# Motorcontroller_V0_6.net
KiCad netlist of a schematic drawn in EAGLE
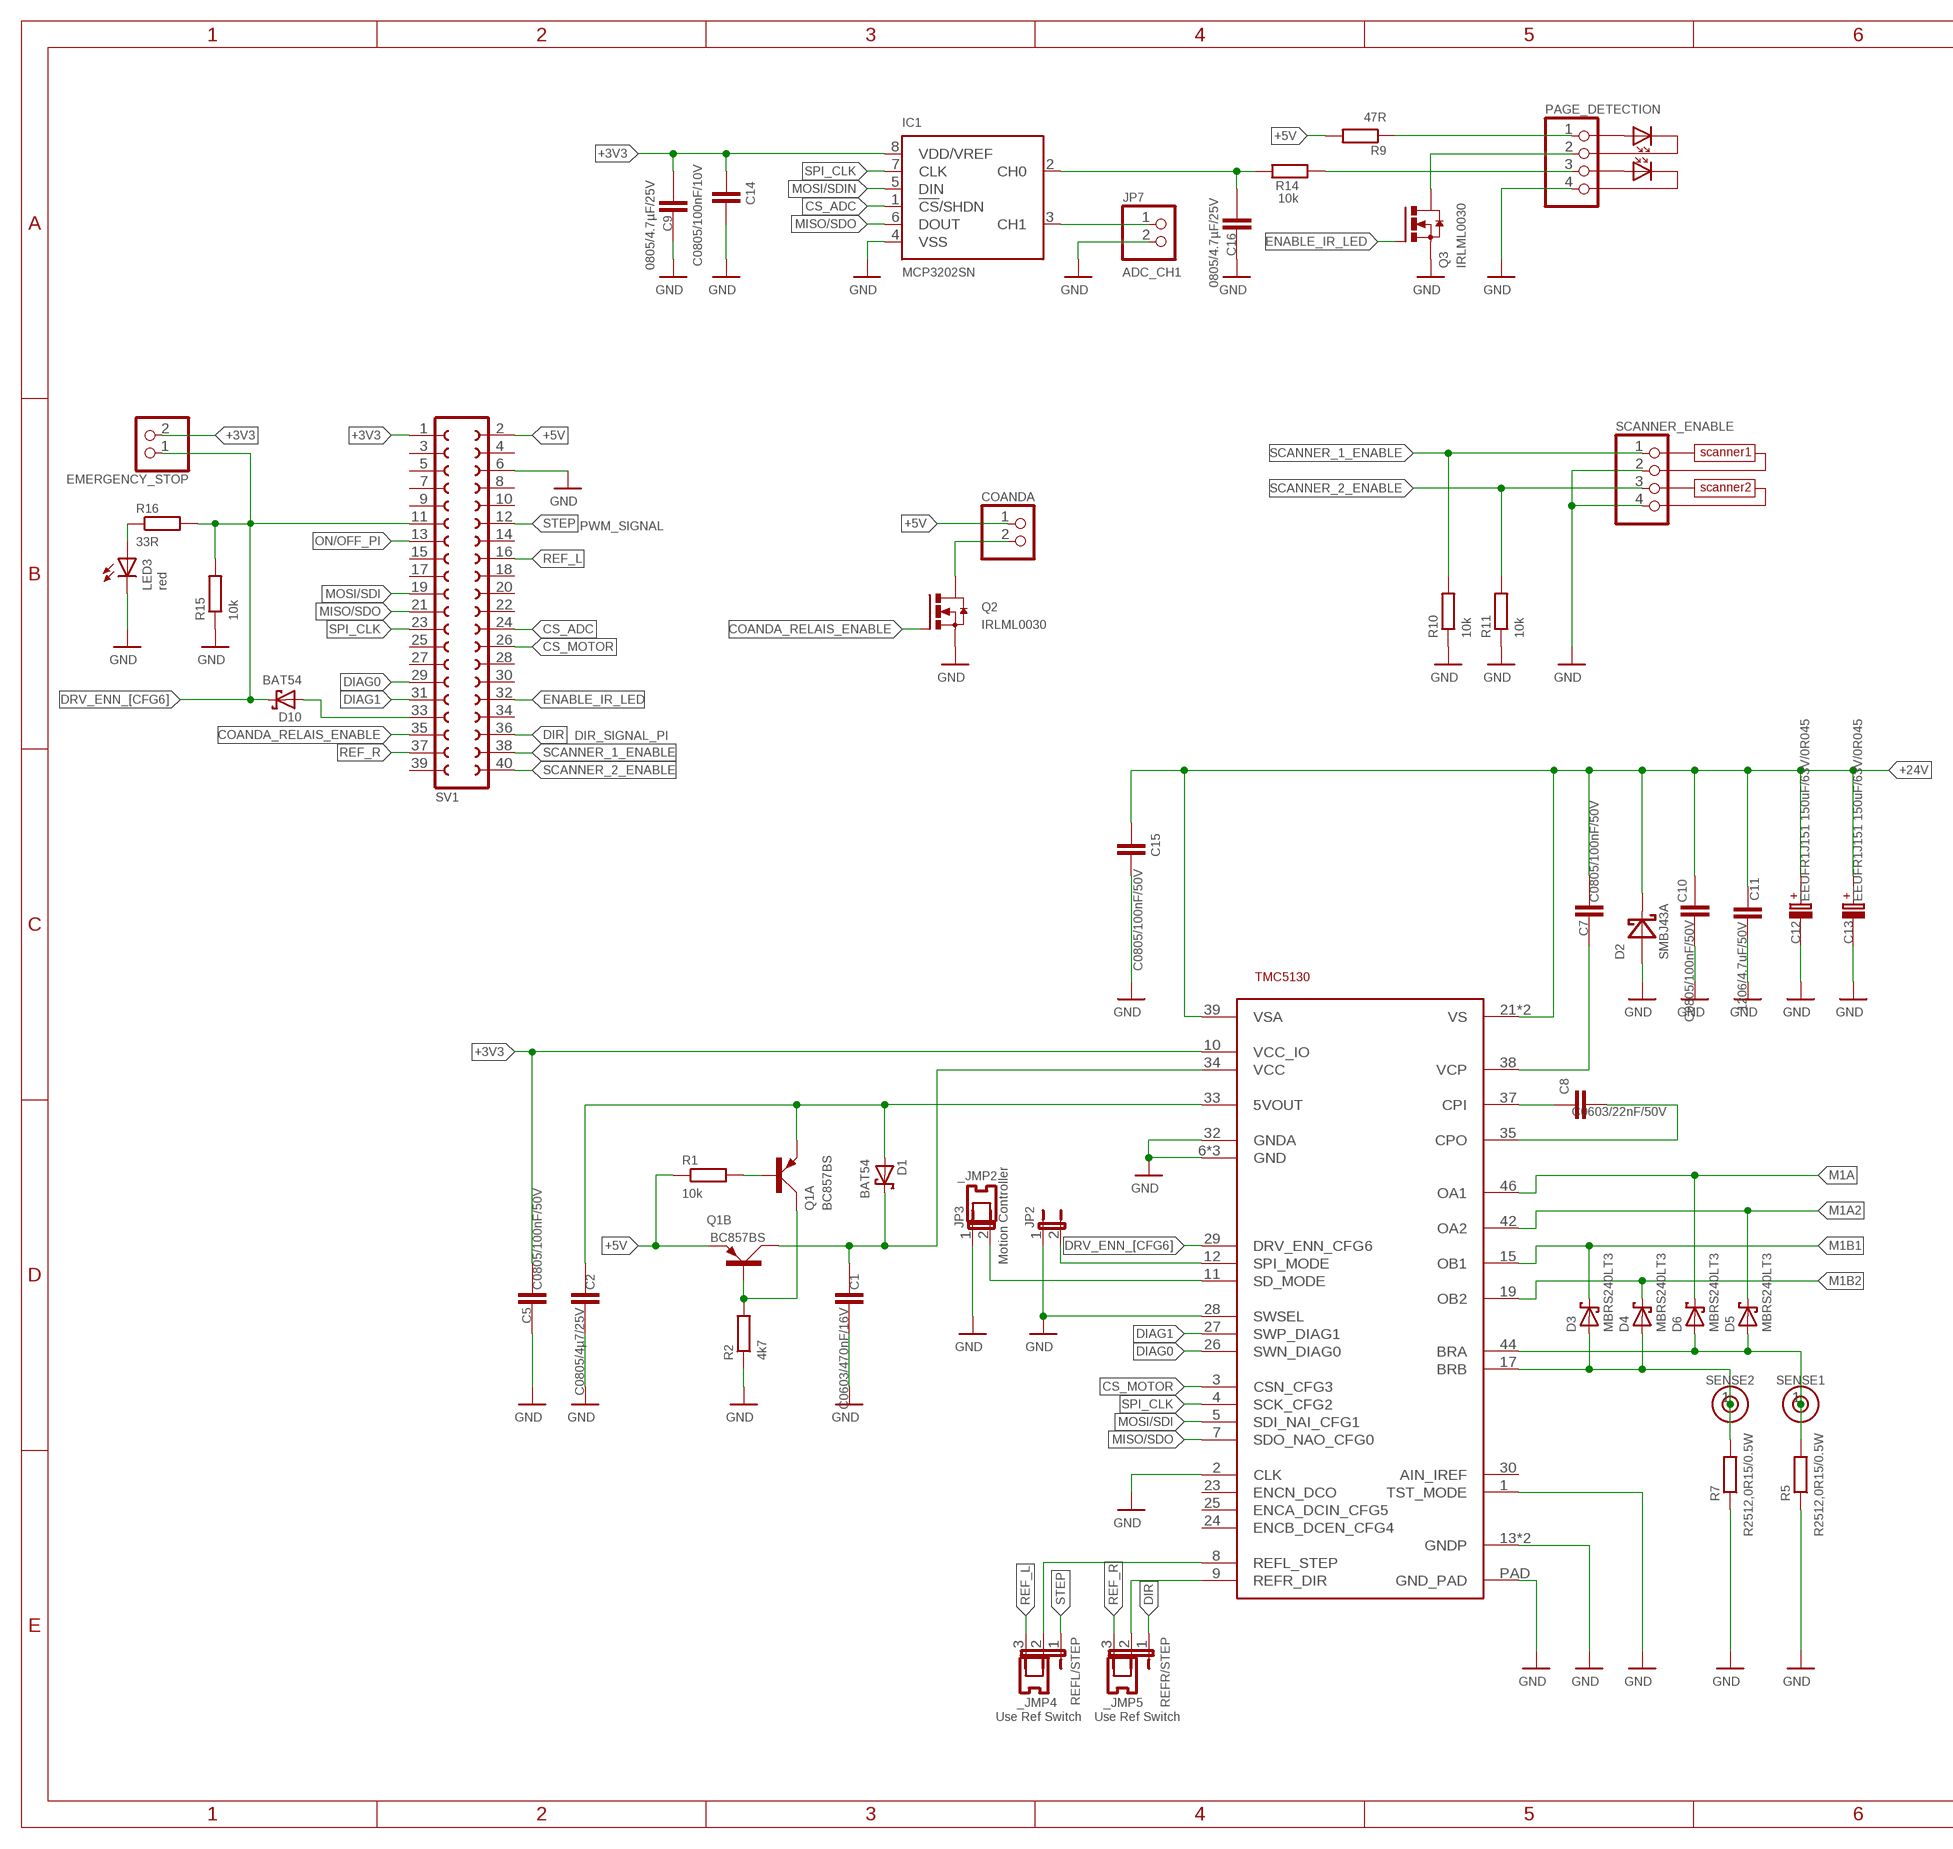
[diagram p0: schematic, sheet 1, part 1 of 2]
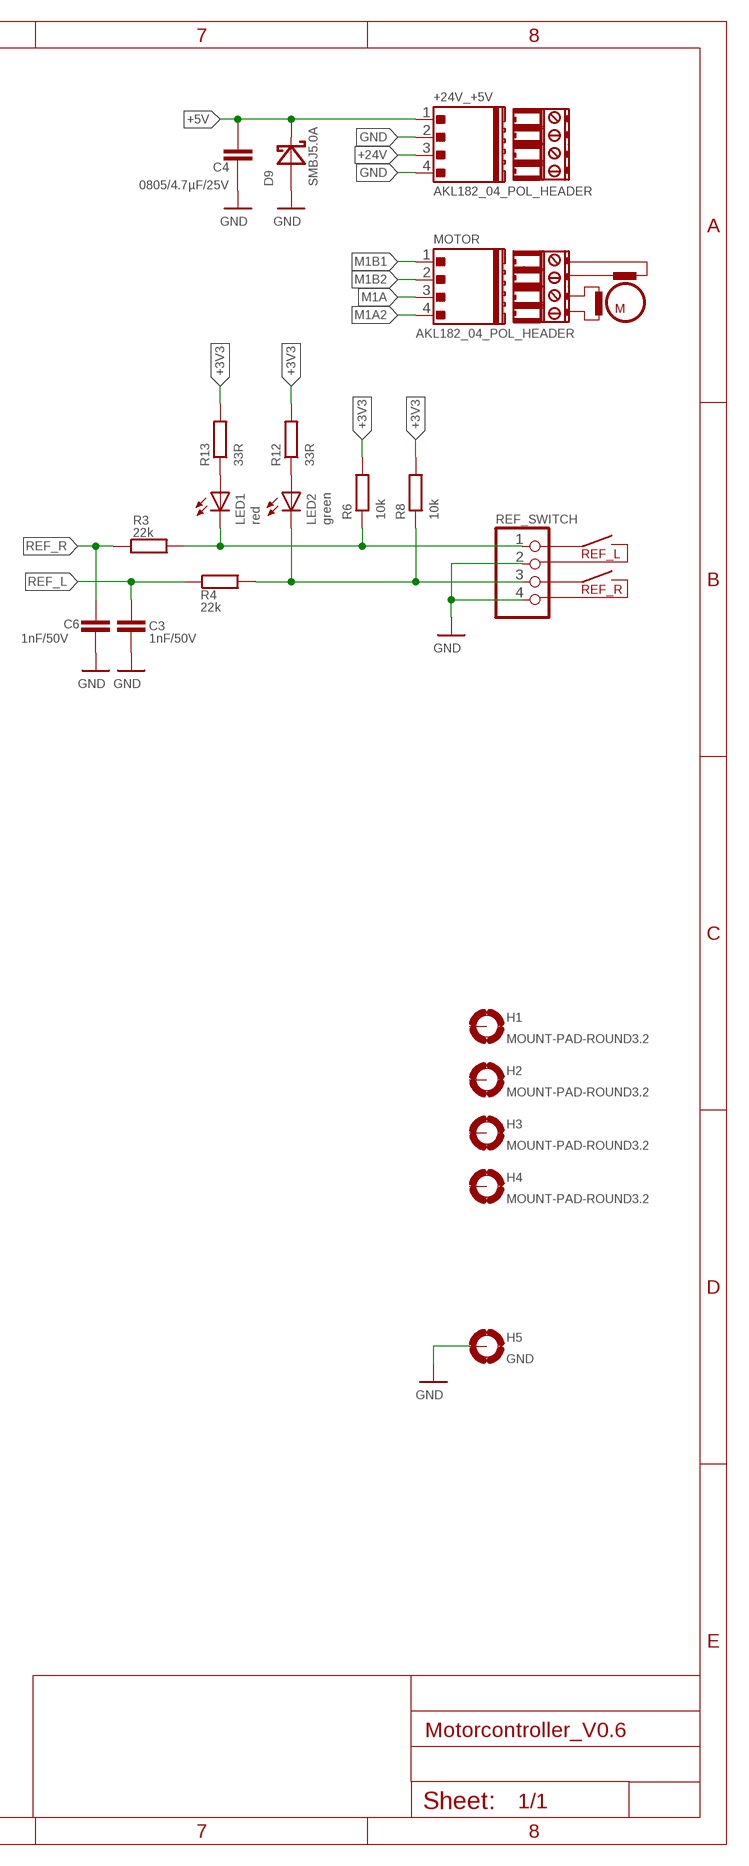
[diagram p1: schematic, sheet 1, part 2 of 2]

(export (version "E")
  (design (tool "Eeschema 10.0.6"))
  (components
    (comp (ref "+24V_+5V")
      (value "AKL182_04_POL_HEADER")
      (footprint "eagle-import:AKL169_04_POL")
      (fields (field (name "1_PARTNUMBER") "31182104") (field (name "2_PARTNUMBER") "AKL 182-04"))
      (libsource (lib "eagle-import") (part "AKL182_04_POL_HEADER"))
    )
    (comp (ref "C1")
      (value "C0603/470nF/16V")
      (footprint "eagle-import:0603")
      (libsource (lib "eagle-import") (part "C/0603"))
    )
    (comp (ref "C2")
      (value "C0805/4µ7/25V")
      (footprint "eagle-import:0805")
      (libsource (lib "eagle-import") (part "C/0805"))
    )
    (comp (ref "C3")
      (value "1nF/50V")
      (footprint "eagle-import:C0603K")
      (libsource (lib "eagle-import") (part "C-EUC0603K"))
    )
    (comp (ref "C4")
      (value "0805/4.7µF/25V")
      (footprint "eagle-import:RCL_0805")
      (libsource (lib "eagle-import") (part "RCL_C/0805"))
    )
    (comp (ref "C5")
      (value "C0805/100nF/50V")
      (footprint "eagle-import:0805")
      (libsource (lib "eagle-import") (part "C/0805"))
    )
    (comp (ref "C6")
      (value "1nF/50V")
      (footprint "eagle-import:C0603K")
      (libsource (lib "eagle-import") (part "C-EUC0603K"))
    )
    (comp (ref "C7")
      (value "C0805/100nF/50V")
      (footprint "eagle-import:0805")
      (libsource (lib "eagle-import") (part "C/0805"))
    )
    (comp (ref "C8")
      (value "C0603/22nF/50V")
      (footprint "eagle-import:C0603")
      (libsource (lib "eagle-import") (part "C-EUC0603"))
    )
    (comp (ref "C9")
      (value "0805/4.7µF/25V")
      (footprint "eagle-import:RCL_0805")
      (libsource (lib "eagle-import") (part "RCL_C/0805"))
    )
    (comp (ref "C10")
      (value "C0805/100nF/50V")
      (footprint "eagle-import:0805")
      (libsource (lib "eagle-import") (part "C/0805"))
    )
    (comp (ref "C11")
      (value "1206/4.7uF/50V")
      (footprint "eagle-import:C1206")
      (libsource (lib "eagle-import") (part "C-EUC1206"))
    )
    (comp (ref "C12")
      (value "EEUFR1J151 150uF/63V/0R045")
      (footprint "eagle-import:C_POL_RAD_THT_5X10X12.5")
      (libsource (lib "eagle-import") (part "C_POL"))
    )
    (comp (ref "C13")
      (value "EEUFR1J151 150uF/63V/0R045")
      (footprint "eagle-import:C_POL_RAD_THT_5X10X12.5")
      (libsource (lib "eagle-import") (part "C_POL"))
    )
    (comp (ref "C14")
      (value "C0805/100nF/10V")
      (footprint "eagle-import:C0805")
      (libsource (lib "eagle-import") (part "C-EUC0805"))
    )
    (comp (ref "C15")
      (value "C0805/100nF/50V")
      (footprint "eagle-import:C0805")
      (libsource (lib "eagle-import") (part "C-EUC0805"))
    )
    (comp (ref "C16")
      (value "0805/4.7µF/25V")
      (footprint "eagle-import:RCL_0805")
      (libsource (lib "eagle-import") (part "RCL_C/0805"))
    )
    (comp (ref "COANDA")
      (value "PINHD-1X2")
      (footprint "eagle-import:1X02")
      (libsource (lib "eagle-import") (part "PINHD-1X2"))
    )
    (comp (ref "D1")
      (value "BAT54")
      (footprint "eagle-import:SOT23")
      (libsource (lib "eagle-import") (part "BAT54"))
    )
    (comp (ref "D2")
      (value "SMBJ43A")
      (footprint "eagle-import:SMB")
      (libsource (lib "eagle-import") (part "SMBJ"))
    )
    (comp (ref "D3")
      (value "MBRS240LT3")
      (footprint "eagle-import:SMB")
      (libsource (lib "eagle-import") (part "MBRS130LT3"))
    )
    (comp (ref "D4")
      (value "MBRS240LT3")
      (footprint "eagle-import:SMB")
      (libsource (lib "eagle-import") (part "MBRS130LT3"))
    )
    (comp (ref "D5")
      (value "MBRS240LT3")
      (footprint "eagle-import:SMB")
      (libsource (lib "eagle-import") (part "MBRS130LT3"))
    )
    (comp (ref "D6")
      (value "MBRS240LT3")
      (footprint "eagle-import:SMB")
      (libsource (lib "eagle-import") (part "MBRS130LT3"))
    )
    (comp (ref "D9")
      (value "SMBJ5.0A")
      (footprint "eagle-import:SMB")
      (libsource (lib "eagle-import") (part "SMBJ"))
    )
    (comp (ref "D10")
      (value "BAT54")
      (footprint "eagle-import:SOT23")
      (libsource (lib "eagle-import") (part "BAT54"))
    )
    (comp (ref "EMERGENCY_STOP")
      (value "PINHD-1X2")
      (footprint "eagle-import:1X02")
      (libsource (lib "eagle-import") (part "PINHD-1X2"))
    )
    (comp (ref "H1")
      (value "MOUNT-PAD-ROUND3.2")
      (footprint "eagle-import:3,2-PAD")
      (libsource (lib "eagle-import") (part "MOUNT-PAD-ROUND3.2"))
    )
    (comp (ref "H2")
      (value "MOUNT-PAD-ROUND3.2")
      (footprint "eagle-import:3,2-PAD")
      (libsource (lib "eagle-import") (part "MOUNT-PAD-ROUND3.2"))
    )
    (comp (ref "H3")
      (value "MOUNT-PAD-ROUND3.2")
      (footprint "eagle-import:3,2-PAD")
      (libsource (lib "eagle-import") (part "MOUNT-PAD-ROUND3.2"))
    )
    (comp (ref "H4")
      (value "MOUNT-PAD-ROUND3.2")
      (footprint "eagle-import:3,2-PAD")
      (libsource (lib "eagle-import") (part "MOUNT-PAD-ROUND3.2"))
    )
    (comp (ref "H5")
      (value "GND")
      (footprint "eagle-import:3,2-PAD")
      (libsource (lib "eagle-import") (part "MOUNT-PAD-ROUND3.2"))
    )
    (comp (ref "IC1")
      (value "MCP3202SN")
      (footprint "eagle-import:SO-08")
      (fields (field (name "MF") "MICROCHIP") (field (name "MPN") "MCP3202-CI/SN"))
      (libsource (lib "eagle-import") (part "MCP3202SN"))
    )
    (comp (ref "JP2")
      (value "JP1E")
      (footprint "eagle-import:JP1")
      (libsource (lib "eagle-import") (part "JP1E"))
    )
    (comp (ref "JP3")
      (value "JP1E")
      (footprint "eagle-import:JP1")
      (libsource (lib "eagle-import") (part "JP1E"))
    )
    (comp (ref "JP7")
      (value "ADC_CH1")
      (footprint "eagle-import:1X02")
      (libsource (lib "eagle-import") (part "PINHD-1X2"))
    )
    (comp (ref "LED1")
      (value "red")
      (footprint "eagle-import:CHIP-LED0805")
      (libsource (lib "eagle-import") (part "LEDCHIP-LED0805"))
    )
    (comp (ref "LED2")
      (value "green")
      (footprint "eagle-import:CHIP-LED0805")
      (libsource (lib "eagle-import") (part "LEDCHIP-LED0805"))
    )
    (comp (ref "LED3")
      (value "red")
      (footprint "eagle-import:CHIP-LED0805")
      (libsource (lib "eagle-import") (part "LEDCHIP-LED0805"))
    )
    (comp (ref "MOTOR")
      (value "AKL182_04_POL_HEADER")
      (footprint "eagle-import:AKL169_04_POL")
      (fields (field (name "1_PARTNUMBER") "31182104") (field (name "2_PARTNUMBER") "AKL 182-04"))
      (libsource (lib "eagle-import") (part "AKL182_04_POL_HEADER"))
    )
    (comp (ref "PAGE_DETECTION")
      (value "PINHD-1X4")
      (footprint "eagle-import:1X04")
      (libsource (lib "eagle-import") (part "PINHD-1X4"))
    )
    (comp (ref "Q1")
      (value "BC857BS")
      (footprint "eagle-import:SOT363_PHILIPS")
      (libsource (lib "eagle-import") (part "BC857BS"))
    )
    (comp (ref "Q2")
      (value "IRLML0030")
      (footprint "eagle-import:SOT-23")
      (libsource (lib "eagle-import") (part "IRLML0030"))
    )
    (comp (ref "Q3")
      (value "IRLML0030")
      (footprint "eagle-import:SOT-23")
      (libsource (lib "eagle-import") (part "IRLML0030"))
    )
    (comp (ref "R1")
      (value "10k")
      (footprint "eagle-import:M0805")
      (libsource (lib "eagle-import") (part "R-EU_M0805"))
    )
    (comp (ref "R2")
      (value "4k7")
      (footprint "eagle-import:M0805")
      (libsource (lib "eagle-import") (part "R-EU_M0805"))
    )
    (comp (ref "R3")
      (value "22k")
      (footprint "eagle-import:R0603")
      (libsource (lib "eagle-import") (part "R-EU_R0603"))
    )
    (comp (ref "R4")
      (value "22k")
      (footprint "eagle-import:R0603")
      (libsource (lib "eagle-import") (part "R-EU_R0603"))
    )
    (comp (ref "R5")
      (value "R2512,0R15/0.5W")
      (footprint "eagle-import:R2512")
      (libsource (lib "eagle-import") (part "R-EU_R2512"))
    )
    (comp (ref "R6")
      (value "10k")
      (footprint "eagle-import:M0805")
      (libsource (lib "eagle-import") (part "R-EU_M0805"))
    )
    (comp (ref "R7")
      (value "R2512,0R15/0.5W")
      (footprint "eagle-import:R2512")
      (libsource (lib "eagle-import") (part "R-EU_R2512"))
    )
    (comp (ref "R8")
      (value "10k")
      (footprint "eagle-import:M0805")
      (libsource (lib "eagle-import") (part "R-EU_M0805"))
    )
    (comp (ref "R9")
      (value "47R")
      (footprint "eagle-import:M1206")
      (libsource (lib "eagle-import") (part "R-EU_M1206"))
    )
    (comp (ref "R10")
      (value "10k")
      (footprint "eagle-import:M0805")
      (libsource (lib "eagle-import") (part "R-EU_M0805"))
    )
    (comp (ref "R11")
      (value "10k")
      (footprint "eagle-import:M0805")
      (libsource (lib "eagle-import") (part "R-EU_M0805"))
    )
    (comp (ref "R12")
      (value "33R")
      (footprint "eagle-import:M0805")
      (libsource (lib "eagle-import") (part "R-EU_M0805"))
    )
    (comp (ref "R13")
      (value "33R")
      (footprint "eagle-import:M0805")
      (libsource (lib "eagle-import") (part "R-EU_M0805"))
    )
    (comp (ref "R14")
      (value "10k")
      (footprint "eagle-import:M0805")
      (libsource (lib "eagle-import") (part "R-EU_M0805"))
    )
    (comp (ref "R15")
      (value "10k")
      (footprint "eagle-import:M0805")
      (libsource (lib "eagle-import") (part "R-EU_M0805"))
    )
    (comp (ref "R16")
      (value "33R")
      (footprint "eagle-import:M0805")
      (libsource (lib "eagle-import") (part "R-EU_M0805"))
    )
    (comp (ref "REFL/STEP")
      (value "JP2E")
      (footprint "eagle-import:JP2")
      (libsource (lib "eagle-import") (part "JP2E"))
    )
    (comp (ref "REFR/STEP")
      (value "JP2E")
      (footprint "eagle-import:JP2")
      (libsource (lib "eagle-import") (part "JP2E"))
    )
    (comp (ref "REF_SWITCH")
      (value "PINHD-1X4")
      (footprint "eagle-import:1X04")
      (libsource (lib "eagle-import") (part "PINHD-1X4"))
    )
    (comp (ref "SCANNER_ENABLE")
      (value "PINHD-1X4")
      (footprint "eagle-import:1X04")
      (libsource (lib "eagle-import") (part "PINHD-1X4"))
    )
    (comp (ref "SENSE1")
      (value "1PIN_1ROW")
      (footprint "eagle-import:1PIN_1ROW_THT")
      (libsource (lib "eagle-import") (part "1PIN_1ROW"))
    )
    (comp (ref "SENSE2")
      (value "1PIN_1ROW")
      (footprint "eagle-import:1PIN_1ROW_THT")
      (libsource (lib "eagle-import") (part "1PIN_1ROW"))
    )
    (comp (ref "SV1")
      (value "FE20-2")
      (footprint "eagle-import:FE20-2")
      (libsource (lib "eagle-import") (part "FE20-2"))
    )
    (comp (ref "TERM1")
      (value "AKL182_04_POL_TERMINAL")
      (footprint "eagle-import:EXTRA_TERMINAL")
      (fields (field (name "1_PARTNUMBER") "31169104") (field (name "2_PARTNUMBER") "AKL 169-04"))
      (libsource (lib "eagle-import") (part "AKL182_04_POL_TERMINAL"))
    )
    (comp (ref "TERM3")
      (value "AKL182_04_POL_TERMINAL")
      (footprint "eagle-import:EXTRA_TERMINAL")
      (fields (field (name "1_PARTNUMBER") "31169104") (field (name "2_PARTNUMBER") "AKL 169-04"))
      (libsource (lib "eagle-import") (part "AKL182_04_POL_TERMINAL"))
    )
    (comp (ref "TMC5130")
      (value "TMC5130")
      (footprint "eagle-import:QFP50P900X900X113-49N_NOFID")
      (libsource (lib "eagle-import") (part "TMC5130"))
    )
  )
  (nets
    (net (code "1") (name "+3V3") (class "Default")
      (node (ref "C14") (pin "2") (pinfunction "2_2") (pintype "passive"))
      (node (ref "C5") (pin "1") (pinfunction "1_1") (pintype "passive"))
      (node (ref "C9") (pin "1") (pinfunction "1_1") (pintype "passive"))
      (node (ref "EMERGENCY_STOP") (pin "2") (pinfunction "2_2") (pintype "passive"))
      (node (ref "IC1") (pin "8") (pinfunction "VDD/VREF_8") (pintype "input"))
      (node (ref "R12") (pin "2") (pinfunction "2_2") (pintype "passive"))
      (node (ref "R13") (pin "2") (pinfunction "2_2") (pintype "passive"))
      (node (ref "R6") (pin "2") (pinfunction "2_2") (pintype "passive"))
      (node (ref "R8") (pin "2") (pinfunction "2_2") (pintype "passive"))
      (node (ref "SV1") (pin "1") (pinfunction "1_1") (pintype "passive"))
      (node (ref "TMC5130") (pin "10") (pinfunction "VCC_IO_10") (pintype "bidirectional"))
    )
    (net (code "2") (name "+5V") (class "Default")
      (node (ref "+24V_+5V") (pin "1") (pinfunction "1_1") (pintype "bidirectional"))
      (node (ref "C4") (pin "1") (pinfunction "1_1") (pintype "passive"))
      (node (ref "COANDA") (pin "1") (pinfunction "1_1") (pintype "passive"))
      (node (ref "D9") (pin "C") (pinfunction "C_C") (pintype "bidirectional"))
      (node (ref "Q1") (pin "4") (pinfunction "E_4") (pintype "passive"))
      (node (ref "R1") (pin "1") (pinfunction "1_1") (pintype "passive"))
      (node (ref "R9") (pin "2") (pinfunction "2_2") (pintype "passive"))
      (node (ref "SV1") (pin "2") (pinfunction "2_2") (pintype "passive"))
    )
    (net (code "3") (name "+24V") (class "Default")
      (node (ref "+24V_+5V") (pin "3") (pinfunction "3_3") (pintype "bidirectional"))
      (node (ref "C10") (pin "2") (pinfunction "2_2") (pintype "passive"))
      (node (ref "C11") (pin "1") (pinfunction "1_1") (pintype "passive"))
      (node (ref "C12") (pin "+") (pinfunction "+_+") (pintype "passive"))
      (node (ref "C13") (pin "+") (pinfunction "+_+") (pintype "passive"))
      (node (ref "C15") (pin "2") (pinfunction "2_2") (pintype "passive"))
      (node (ref "C7") (pin "1") (pinfunction "1_1") (pintype "passive"))
      (node (ref "D2") (pin "C") (pinfunction "C_C") (pintype "bidirectional"))
      (node (ref "TMC5130") (pin "21") (pinfunction "VS_21") (pintype "bidirectional"))
      (node (ref "TMC5130") (pin "39") (pinfunction "VSA_39") (pintype "bidirectional"))
      (node (ref "TMC5130") (pin "40") (pinfunction "VS_40") (pintype "bidirectional"))
    )
    (net (code "4") (name "COANDA_RELAIS_ENABLE") (class "Default")
      (node (ref "Q2") (pin "1") (pinfunction "G_1") (pintype "passive"))
      (node (ref "SV1") (pin "35") (pinfunction "35_35") (pintype "passive"))
    )
    (net (code "5") (name "CS_ADC") (class "Default")
      (node (ref "IC1") (pin "1") (pinfunction "~{CS}/SHDN_1") (pintype "input"))
      (node (ref "SV1") (pin "24") (pinfunction "24_24") (pintype "passive"))
    )
    (net (code "6") (name "CS_MOTOR") (class "Default")
      (node (ref "SV1") (pin "26") (pinfunction "26_26") (pintype "passive"))
      (node (ref "TMC5130") (pin "3") (pinfunction "CSN_CFG3_3") (pintype "bidirectional"))
    )
    (net (code "7") (name "DIAG0") (class "Default")
      (node (ref "SV1") (pin "29") (pinfunction "29_29") (pintype "passive"))
      (node (ref "TMC5130") (pin "26") (pinfunction "SWN_DIAG0_26") (pintype "bidirectional"))
    )
    (net (code "8") (name "DIAG1") (class "Default")
      (node (ref "SV1") (pin "31") (pinfunction "31_31") (pintype "passive"))
      (node (ref "TMC5130") (pin "27") (pinfunction "SWP_DIAG1_27") (pintype "bidirectional"))
    )
    (net (code "9") (name "DIR") (class "Default")
      (node (ref "REFR/STEP") (pin "1") (pinfunction "1_1") (pintype "passive"))
      (node (ref "SV1") (pin "36") (pinfunction "36_36") (pintype "passive"))
    )
    (net (code "10") (name "DRV_ENN_[CFG6]") (class "Default")
      (node (ref "D10") (pin "3") (pinfunction "C_3") (pintype "passive"))
      (node (ref "EMERGENCY_STOP") (pin "1") (pinfunction "1_1") (pintype "passive"))
      (node (ref "R15") (pin "2") (pinfunction "2_2") (pintype "passive"))
      (node (ref "R16") (pin "2") (pinfunction "2_2") (pintype "passive"))
      (node (ref "SV1") (pin "11") (pinfunction "11_11") (pintype "passive"))
      (node (ref "TMC5130") (pin "29") (pinfunction "DRV_ENN_CFG6_29") (pintype "bidirectional"))
    )
    (net (code "11") (name "ENABLE_IR_LED") (class "Default")
      (node (ref "Q3") (pin "1") (pinfunction "G_1") (pintype "passive"))
      (node (ref "SV1") (pin "32") (pinfunction "32_32") (pintype "passive"))
    )
    (net (code "12") (name "GND") (class "Default")
      (node (ref "+24V_+5V") (pin "2") (pinfunction "2_2") (pintype "bidirectional"))
      (node (ref "+24V_+5V") (pin "4") (pinfunction "4_4") (pintype "bidirectional"))
      (node (ref "C1") (pin "1") (pinfunction "1_1") (pintype "passive"))
      (node (ref "C10") (pin "1") (pinfunction "1_1") (pintype "passive"))
      (node (ref "C11") (pin "2") (pinfunction "2_2") (pintype "passive"))
      (node (ref "C12") (pin "-") (pinfunction "-_-") (pintype "passive"))
      (node (ref "C13") (pin "-") (pinfunction "-_-") (pintype "passive"))
      (node (ref "C14") (pin "1") (pinfunction "1_1") (pintype "passive"))
      (node (ref "C15") (pin "1") (pinfunction "1_1") (pintype "passive"))
      (node (ref "C16") (pin "2") (pinfunction "2_2") (pintype "passive"))
      (node (ref "C2") (pin "1") (pinfunction "1_1") (pintype "passive"))
      (node (ref "C3") (pin "1") (pinfunction "1_1") (pintype "passive"))
      (node (ref "C4") (pin "2") (pinfunction "2_2") (pintype "passive"))
      (node (ref "C5") (pin "2") (pinfunction "2_2") (pintype "passive"))
      (node (ref "C6") (pin "1") (pinfunction "1_1") (pintype "passive"))
      (node (ref "C9") (pin "2") (pinfunction "2_2") (pintype "passive"))
      (node (ref "D2") (pin "A") (pinfunction "A_A") (pintype "bidirectional"))
      (node (ref "D9") (pin "A") (pinfunction "A_A") (pintype "bidirectional"))
      (node (ref "H5") (pin "B3,2") (pinfunction "MOUNT_B3,2") (pintype "passive"))
      (node (ref "IC1") (pin "4") (pinfunction "VSS_4") (pintype "input"))
      (node (ref "JP2") (pin "1") (pinfunction "1_1") (pintype "passive"))
      (node (ref "JP3") (pin "1") (pinfunction "1_1") (pintype "passive"))
      (node (ref "JP7") (pin "2") (pinfunction "2_2") (pintype "passive"))
      (node (ref "LED3") (pin "C") (pinfunction "C_C") (pintype "passive"))
      (node (ref "PAGE_DETECTION") (pin "4") (pinfunction "4_4") (pintype "passive"))
      (node (ref "Q2") (pin "2") (pinfunction "S_2") (pintype "passive"))
      (node (ref "Q3") (pin "2") (pinfunction "S_2") (pintype "passive"))
      (node (ref "R10") (pin "1") (pinfunction "1_1") (pintype "passive"))
      (node (ref "R11") (pin "1") (pinfunction "1_1") (pintype "passive"))
      (node (ref "R15") (pin "1") (pinfunction "1_1") (pintype "passive"))
      (node (ref "R2") (pin "1") (pinfunction "1_1") (pintype "passive"))
      (node (ref "R5") (pin "1") (pinfunction "1_1") (pintype "passive"))
      (node (ref "R7") (pin "1") (pinfunction "1_1") (pintype "passive"))
      (node (ref "REF_SWITCH") (pin "2") (pinfunction "2_2") (pintype "passive"))
      (node (ref "REF_SWITCH") (pin "4") (pinfunction "4_4") (pintype "passive"))
      (node (ref "SCANNER_ENABLE") (pin "2") (pinfunction "2_2") (pintype "passive"))
      (node (ref "SCANNER_ENABLE") (pin "4") (pinfunction "4_4") (pintype "passive"))
      (node (ref "SV1") (pin "6") (pinfunction "6_6") (pintype "passive"))
      (node (ref "TMC5130") (pin "1") (pinfunction "TST_MODE_1") (pintype "bidirectional"))
      (node (ref "TMC5130") (pin "13") (pinfunction "GNDP_13") (pintype "bidirectional"))
      (node (ref "TMC5130") (pin "2") (pinfunction "CLK_2") (pintype "bidirectional"))
      (node (ref "TMC5130") (pin "28") (pinfunction "SWSEL_28") (pintype "bidirectional"))
      (node (ref "TMC5130") (pin "31") (pinfunction "GND_31") (pintype "bidirectional"))
      (node (ref "TMC5130") (pin "32") (pinfunction "GNDA_32") (pintype "bidirectional"))
      (node (ref "TMC5130") (pin "36") (pinfunction "GND_36") (pintype "bidirectional"))
      (node (ref "TMC5130") (pin "48") (pinfunction "GNDP_48") (pintype "bidirectional"))
      (node (ref "TMC5130") (pin "6") (pinfunction "GND_6") (pintype "bidirectional"))
      (node (ref "TMC5130") (pin "PAD") (pinfunction "GND_PAD_PAD") (pintype "bidirectional"))
    )
    (net (code "13") (name "M1A") (class "Default")
      (node (ref "D6") (pin "C") (pinfunction "C_C") (pintype "passive"))
      (node (ref "MOTOR") (pin "3") (pinfunction "3_3") (pintype "bidirectional"))
      (node (ref "TMC5130") (pin "46") (pinfunction "OA1_46") (pintype "bidirectional"))
    )
    (net (code "14") (name "M1A2") (class "Default")
      (node (ref "D5") (pin "C") (pinfunction "C_C") (pintype "passive"))
      (node (ref "MOTOR") (pin "4") (pinfunction "4_4") (pintype "bidirectional"))
      (node (ref "TMC5130") (pin "42") (pinfunction "OA2_42") (pintype "bidirectional"))
    )
    (net (code "15") (name "M1B1") (class "Default")
      (node (ref "D3") (pin "C") (pinfunction "C_C") (pintype "passive"))
      (node (ref "MOTOR") (pin "1") (pinfunction "1_1") (pintype "bidirectional"))
      (node (ref "TMC5130") (pin "15") (pinfunction "OB1_15") (pintype "bidirectional"))
    )
    (net (code "16") (name "M1B2") (class "Default")
      (node (ref "D4") (pin "C") (pinfunction "C_C") (pintype "passive"))
      (node (ref "MOTOR") (pin "2") (pinfunction "2_2") (pintype "bidirectional"))
      (node (ref "TMC5130") (pin "19") (pinfunction "OB2_19") (pintype "bidirectional"))
    )
    (net (code "17") (name "MISO{slash}SDO") (class "Default")
      (node (ref "IC1") (pin "6") (pinfunction "DOUT_6") (pintype "input"))
      (node (ref "SV1") (pin "21") (pinfunction "21_21") (pintype "passive"))
      (node (ref "TMC5130") (pin "7") (pinfunction "SDO_NAO_CFG0_7") (pintype "bidirectional"))
    )
    (net (code "18") (name "MOSI{slash}SDI") (class "Default")
      (node (ref "SV1") (pin "19") (pinfunction "19_19") (pintype "passive"))
      (node (ref "TMC5130") (pin "5") (pinfunction "SDI_NAI_CFG1_5") (pintype "bidirectional"))
    )
    (net (code "19") (name "MOSI{slash}SDIN") (class "Default")
      (node (ref "IC1") (pin "5") (pinfunction "DIN_5") (pintype "input"))
    )
    (net (code "20") (name "Net-(D1-A)") (class "Default")
      (node (ref "C2") (pin "2") (pinfunction "2_2") (pintype "passive"))
      (node (ref "D1") (pin "1") (pinfunction "A_1") (pintype "passive"))
      (node (ref "Q1") (pin "1") (pinfunction "E_1") (pintype "passive"))
      (node (ref "TMC5130") (pin "33") (pinfunction "5VOUT_33") (pintype "bidirectional"))
    )
    (net (code "21") (name "Net-(D1-C)") (class "Default")
      (node (ref "C1") (pin "2") (pinfunction "2_2") (pintype "passive"))
      (node (ref "D1") (pin "3") (pinfunction "C_3") (pintype "passive"))
      (node (ref "Q1") (pin "3") (pinfunction "C_3") (pintype "passive"))
      (node (ref "TMC5130") (pin "34") (pinfunction "VCC_34") (pintype "bidirectional"))
    )
    (net (code "22") (name "Net-(D10-A)") (class "Default")
      (node (ref "D10") (pin "1") (pinfunction "A_1") (pintype "passive"))
      (node (ref "SV1") (pin "33") (pinfunction "33_33") (pintype "passive"))
    )
    (net (code "23") (name "Net-(IC1-CH0)") (class "Default")
      (node (ref "C16") (pin "1") (pinfunction "1_1") (pintype "passive"))
      (node (ref "IC1") (pin "2") (pinfunction "CH0_2") (pintype "input"))
      (node (ref "R14") (pin "2") (pinfunction "2_2") (pintype "passive"))
    )
    (net (code "24") (name "Net-(IC1-CH1)") (class "Default")
      (node (ref "IC1") (pin "3") (pinfunction "CH1_3") (pintype "input"))
      (node (ref "JP7") (pin "1") (pinfunction "1_1") (pintype "passive"))
    )
    (net (code "25") (name "Net-(LED1-PadA)") (class "Default")
      (node (ref "LED1") (pin "A") (pinfunction "A_A") (pintype "passive"))
      (node (ref "R13") (pin "1") (pinfunction "1_1") (pintype "passive"))
    )
    (net (code "26") (name "Net-(LED1-PadC)") (class "Default")
      (node (ref "LED1") (pin "C") (pinfunction "C_C") (pintype "passive"))
      (node (ref "R3") (pin "2") (pinfunction "2_2") (pintype "passive"))
      (node (ref "R6") (pin "1") (pinfunction "1_1") (pintype "passive"))
      (node (ref "REF_SWITCH") (pin "1") (pinfunction "1_1") (pintype "passive"))
    )
    (net (code "27") (name "Net-(LED2-PadA)") (class "Default")
      (node (ref "LED2") (pin "A") (pinfunction "A_A") (pintype "passive"))
      (node (ref "R12") (pin "1") (pinfunction "1_1") (pintype "passive"))
    )
    (net (code "28") (name "Net-(LED2-PadC)") (class "Default")
      (node (ref "LED2") (pin "C") (pinfunction "C_C") (pintype "passive"))
      (node (ref "R4") (pin "2") (pinfunction "2_2") (pintype "passive"))
      (node (ref "R8") (pin "1") (pinfunction "1_1") (pintype "passive"))
      (node (ref "REF_SWITCH") (pin "3") (pinfunction "3_3") (pintype "passive"))
    )
    (net (code "29") (name "Net-(LED3-PadA)") (class "Default")
      (node (ref "LED3") (pin "A") (pinfunction "A_A") (pintype "passive"))
      (node (ref "R16") (pin "1") (pinfunction "1_1") (pintype "passive"))
    )
    (net (code "30") (name "Net-(PAGE_DETECTION-Pad1)") (class "Default")
      (node (ref "PAGE_DETECTION") (pin "1") (pinfunction "1_1") (pintype "passive"))
      (node (ref "R9") (pin "1") (pinfunction "1_1") (pintype "passive"))
    )
    (net (code "31") (name "Net-(PAGE_DETECTION-Pad3)") (class "Default")
      (node (ref "PAGE_DETECTION") (pin "3") (pinfunction "3_3") (pintype "passive"))
      (node (ref "R14") (pin "1") (pinfunction "1_1") (pintype "passive"))
    )
    (net (code "32") (name "Net-(Q1A-B)") (class "Default")
      (node (ref "Q1") (pin "2") (pinfunction "B_2") (pintype "passive"))
      (node (ref "R1") (pin "2") (pinfunction "2_2") (pintype "passive"))
    )
    (net (code "33") (name "Net-(Q1A-C)") (class "Default")
      (node (ref "Q1") (pin "5") (pinfunction "B_5") (pintype "passive"))
      (node (ref "Q1") (pin "6") (pinfunction "C_6") (pintype "passive"))
      (node (ref "R2") (pin "2") (pinfunction "2_2") (pintype "passive"))
    )
    (net (code "34") (name "Net-(Q2-D)") (class "Default")
      (node (ref "COANDA") (pin "2") (pinfunction "2_2") (pintype "passive"))
      (node (ref "Q2") (pin "3") (pinfunction "D_3") (pintype "passive"))
    )
    (net (code "35") (name "Net-(Q3-D)") (class "Default")
      (node (ref "PAGE_DETECTION") (pin "2") (pinfunction "2_2") (pintype "passive"))
      (node (ref "Q3") (pin "3") (pinfunction "D_3") (pintype "passive"))
    )
    (net (code "36") (name "Net-(SENSE1-P$1)") (class "Default")
      (node (ref "D5") (pin "A") (pinfunction "A_A") (pintype "passive"))
      (node (ref "D6") (pin "A") (pinfunction "A_A") (pintype "passive"))
      (node (ref "R5") (pin "2") (pinfunction "2_2") (pintype "passive"))
      (node (ref "SENSE1") (pin "1") (pinfunction "P$1_1") (pintype "bidirectional"))
      (node (ref "TMC5130") (pin "44") (pinfunction "BRA_44") (pintype "bidirectional"))
    )
    (net (code "37") (name "Net-(SENSE2-P$1)") (class "Default")
      (node (ref "D3") (pin "A") (pinfunction "A_A") (pintype "passive"))
      (node (ref "D4") (pin "A") (pinfunction "A_A") (pintype "passive"))
      (node (ref "R7") (pin "2") (pinfunction "2_2") (pintype "passive"))
      (node (ref "SENSE2") (pin "1") (pinfunction "P$1_1") (pintype "bidirectional"))
      (node (ref "TMC5130") (pin "17") (pinfunction "BRB_17") (pintype "bidirectional"))
    )
    (net (code "38") (name "Net-(TMC5130-CPI)") (class "Default")
      (node (ref "C8") (pin "1") (pinfunction "1_1") (pintype "passive"))
      (node (ref "TMC5130") (pin "37") (pinfunction "CPI_37") (pintype "bidirectional"))
    )
    (net (code "39") (name "Net-(TMC5130-CPO)") (class "Default")
      (node (ref "C8") (pin "2") (pinfunction "2_2") (pintype "passive"))
      (node (ref "TMC5130") (pin "35") (pinfunction "CPO_35") (pintype "bidirectional"))
    )
    (net (code "40") (name "Net-(TMC5130-REFL_STEP)") (class "Default")
      (node (ref "REFL/STEP") (pin "2") (pinfunction "2_2") (pintype "passive"))
      (node (ref "TMC5130") (pin "8") (pinfunction "REFL_STEP_8") (pintype "bidirectional"))
    )
    (net (code "41") (name "Net-(TMC5130-REFR_DIR)") (class "Default")
      (node (ref "REFR/STEP") (pin "2") (pinfunction "2_2") (pintype "passive"))
      (node (ref "TMC5130") (pin "9") (pinfunction "REFR_DIR_9") (pintype "bidirectional"))
    )
    (net (code "42") (name "Net-(TMC5130-SD_MODE)") (class "Default")
      (node (ref "JP3") (pin "2") (pinfunction "2_2") (pintype "passive"))
      (node (ref "TMC5130") (pin "11") (pinfunction "SD_MODE_11") (pintype "bidirectional"))
    )
    (net (code "43") (name "Net-(TMC5130-SPI_MODE)") (class "Default")
      (node (ref "JP2") (pin "2") (pinfunction "2_2") (pintype "passive"))
      (node (ref "TMC5130") (pin "12") (pinfunction "SPI_MODE_12") (pintype "bidirectional"))
    )
    (net (code "44") (name "Net-(TMC5130-VCP)") (class "Default")
      (node (ref "C7") (pin "2") (pinfunction "2_2") (pintype "passive"))
      (node (ref "TMC5130") (pin "38") (pinfunction "VCP_38") (pintype "bidirectional"))
    )
    (net (code "45") (name "ON{slash}OFF_PI") (class "Default")
      (node (ref "SV1") (pin "13") (pinfunction "13_13") (pintype "passive"))
    )
    (net (code "46") (name "REF_L") (class "Default")
      (node (ref "C3") (pin "2") (pinfunction "2_2") (pintype "passive"))
      (node (ref "R4") (pin "1") (pinfunction "1_1") (pintype "passive"))
      (node (ref "REFL/STEP") (pin "3") (pinfunction "3_3") (pintype "passive"))
      (node (ref "SV1") (pin "16") (pinfunction "16_16") (pintype "passive"))
    )
    (net (code "47") (name "REF_R") (class "Default")
      (node (ref "C6") (pin "2") (pinfunction "2_2") (pintype "passive"))
      (node (ref "R3") (pin "1") (pinfunction "1_1") (pintype "passive"))
      (node (ref "REFR/STEP") (pin "3") (pinfunction "3_3") (pintype "passive"))
      (node (ref "SV1") (pin "37") (pinfunction "37_37") (pintype "passive"))
    )
    (net (code "48") (name "SCANNER_1_ENABLE") (class "Default")
      (node (ref "R10") (pin "2") (pinfunction "2_2") (pintype "passive"))
      (node (ref "SCANNER_ENABLE") (pin "1") (pinfunction "1_1") (pintype "passive"))
      (node (ref "SV1") (pin "38") (pinfunction "38_38") (pintype "passive"))
    )
    (net (code "49") (name "SCANNER_2_ENABLE") (class "Default")
      (node (ref "R11") (pin "2") (pinfunction "2_2") (pintype "passive"))
      (node (ref "SCANNER_ENABLE") (pin "3") (pinfunction "3_3") (pintype "passive"))
      (node (ref "SV1") (pin "40") (pinfunction "40_40") (pintype "passive"))
    )
    (net (code "50") (name "SPI_CLK") (class "Default")
      (node (ref "IC1") (pin "7") (pinfunction "CLK_7") (pintype "input"))
      (node (ref "SV1") (pin "23") (pinfunction "23_23") (pintype "passive"))
      (node (ref "TMC5130") (pin "4") (pinfunction "SCK_CFG2_4") (pintype "bidirectional"))
    )
    (net (code "51") (name "STEP") (class "Default")
      (node (ref "REFL/STEP") (pin "1") (pinfunction "1_1") (pintype "passive"))
      (node (ref "SV1") (pin "12") (pinfunction "12_12") (pintype "passive"))
    )
    (net (code "52") (name "unconnected-(H1-MOUNT-PadB3,2)") (class "Default")
      (node (ref "H1") (pin "B3,2") (pinfunction "MOUNT_B3,2") (pintype "passive"))
    )
    (net (code "53") (name "unconnected-(H2-MOUNT-PadB3,2)") (class "Default")
      (node (ref "H2") (pin "B3,2") (pinfunction "MOUNT_B3,2") (pintype "passive"))
    )
    (net (code "54") (name "unconnected-(H3-MOUNT-PadB3,2)") (class "Default")
      (node (ref "H3") (pin "B3,2") (pinfunction "MOUNT_B3,2") (pintype "passive"))
    )
    (net (code "55") (name "unconnected-(H4-MOUNT-PadB3,2)") (class "Default")
      (node (ref "H4") (pin "B3,2") (pinfunction "MOUNT_B3,2") (pintype "passive"))
    )
    (net (code "56") (name "unconnected-(SV1-Pad3)") (class "Default")
      (node (ref "SV1") (pin "3") (pinfunction "3_3") (pintype "passive"))
    )
    (net (code "57") (name "unconnected-(SV1-Pad4)") (class "Default")
      (node (ref "SV1") (pin "4") (pinfunction "4_4") (pintype "passive"))
    )
    (net (code "58") (name "unconnected-(SV1-Pad5)") (class "Default")
      (node (ref "SV1") (pin "5") (pinfunction "5_5") (pintype "passive"))
    )
    (net (code "59") (name "unconnected-(SV1-Pad7)") (class "Default")
      (node (ref "SV1") (pin "7") (pinfunction "7_7") (pintype "passive"))
    )
    (net (code "60") (name "unconnected-(SV1-Pad8)") (class "Default")
      (node (ref "SV1") (pin "8") (pinfunction "8_8") (pintype "passive"))
    )
    (net (code "61") (name "unconnected-(SV1-Pad9)") (class "Default")
      (node (ref "SV1") (pin "9") (pinfunction "9_9") (pintype "passive"))
    )
    (net (code "62") (name "unconnected-(SV1-Pad10)") (class "Default")
      (node (ref "SV1") (pin "10") (pinfunction "10_10") (pintype "passive"))
    )
    (net (code "63") (name "unconnected-(SV1-Pad14)") (class "Default")
      (node (ref "SV1") (pin "14") (pinfunction "14_14") (pintype "passive"))
    )
    (net (code "64") (name "unconnected-(SV1-Pad15)") (class "Default")
      (node (ref "SV1") (pin "15") (pinfunction "15_15") (pintype "passive"))
    )
    (net (code "65") (name "unconnected-(SV1-Pad17)") (class "Default")
      (node (ref "SV1") (pin "17") (pinfunction "17_17") (pintype "passive"))
    )
    (net (code "66") (name "unconnected-(SV1-Pad18)") (class "Default")
      (node (ref "SV1") (pin "18") (pinfunction "18_18") (pintype "passive"))
    )
    (net (code "67") (name "unconnected-(SV1-Pad20)") (class "Default")
      (node (ref "SV1") (pin "20") (pinfunction "20_20") (pintype "passive"))
    )
    (net (code "68") (name "unconnected-(SV1-Pad22)") (class "Default")
      (node (ref "SV1") (pin "22") (pinfunction "22_22") (pintype "passive"))
    )
    (net (code "69") (name "unconnected-(SV1-Pad25)") (class "Default")
      (node (ref "SV1") (pin "25") (pinfunction "25_25") (pintype "passive"))
    )
    (net (code "70") (name "unconnected-(SV1-Pad27)") (class "Default")
      (node (ref "SV1") (pin "27") (pinfunction "27_27") (pintype "passive"))
    )
    (net (code "71") (name "unconnected-(SV1-Pad28)") (class "Default")
      (node (ref "SV1") (pin "28") (pinfunction "28_28") (pintype "passive"))
    )
    (net (code "72") (name "unconnected-(SV1-Pad30)") (class "Default")
      (node (ref "SV1") (pin "30") (pinfunction "30_30") (pintype "passive"))
    )
    (net (code "73") (name "unconnected-(SV1-Pad34)") (class "Default")
      (node (ref "SV1") (pin "34") (pinfunction "34_34") (pintype "passive"))
    )
    (net (code "74") (name "unconnected-(SV1-Pad39)") (class "Default")
      (node (ref "SV1") (pin "39") (pinfunction "39_39") (pintype "passive"))
    )
    (net (code "75") (name "unconnected-(TMC5130-AIN_IREF-Pad30)") (class "Default")
      (node (ref "TMC5130") (pin "30") (pinfunction "AIN_IREF_30") (pintype "bidirectional"))
    )
    (net (code "76") (name "unconnected-(TMC5130-ENCA_DCIN_CFG5-Pad25)") (class "Default")
      (node (ref "TMC5130") (pin "25") (pinfunction "ENCA_DCIN_CFG5_25") (pintype "bidirectional"))
    )
    (net (code "77") (name "unconnected-(TMC5130-ENCB_DCEN_CFG4-Pad24)") (class "Default")
      (node (ref "TMC5130") (pin "24") (pinfunction "ENCB_DCEN_CFG4_24") (pintype "bidirectional"))
    )
    (net (code "78") (name "unconnected-(TMC5130-ENCN_DCO-Pad23)") (class "Default")
      (node (ref "TMC5130") (pin "23") (pinfunction "ENCN_DCO_23") (pintype "bidirectional"))
    )
  )
)
